# umotion_2_v1_2_pcb_1.net
KiCad netlist of a schematic drawn in EAGLE
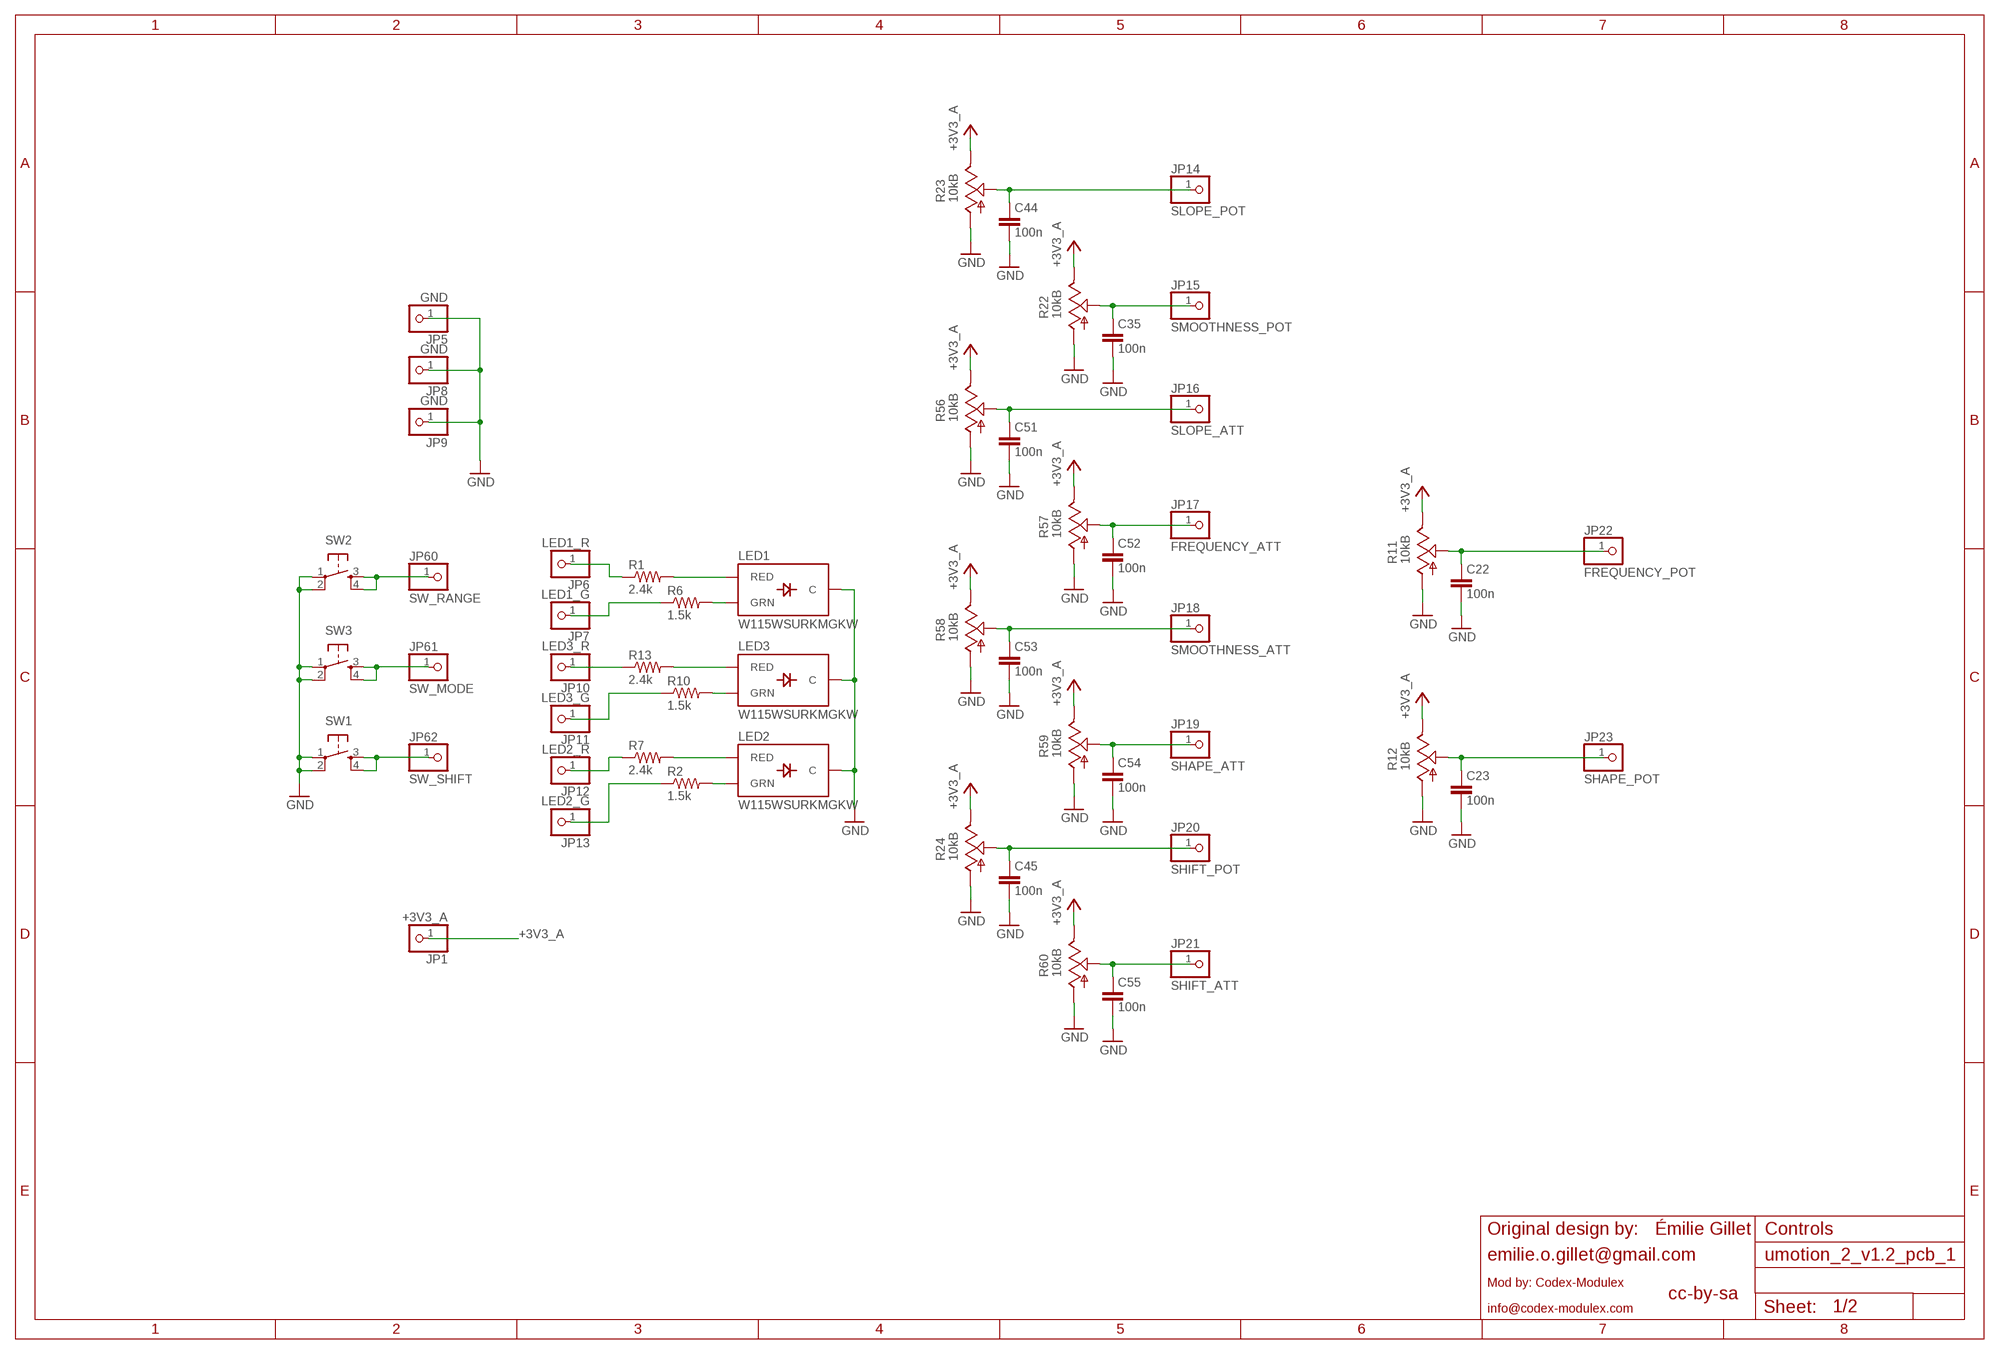
[diagram p0: schematic, sheet 1]
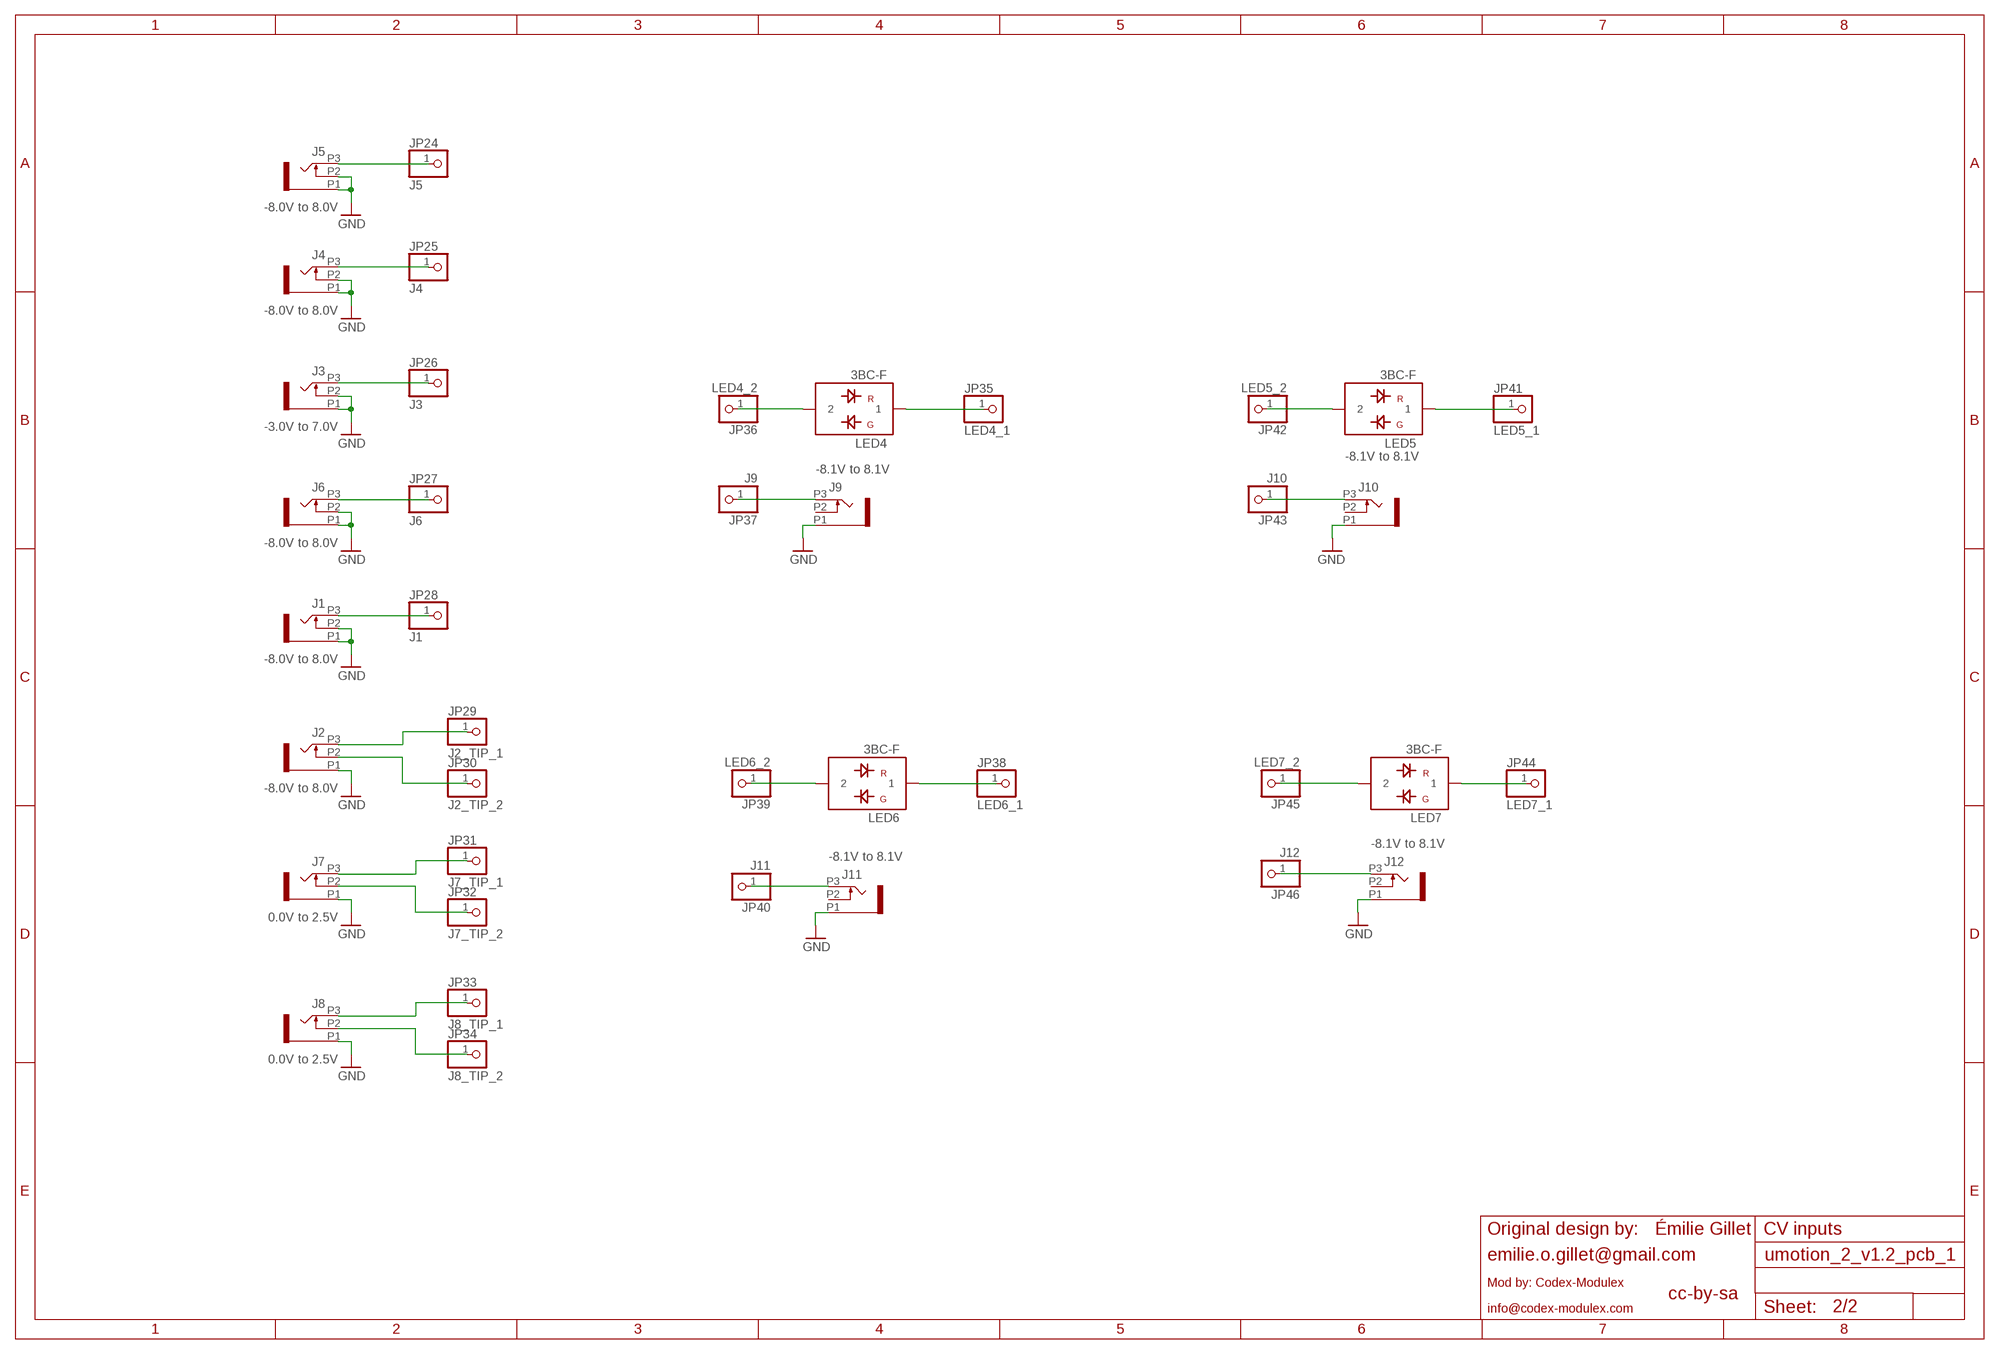
[diagram p1: schematic, sheet 2]

(export (version "E")
  (design (tool "Eeschema 10.0.6"))
  (components
    (comp (ref "J1")
      (value "PJ301_THONKICONN6")
      (footprint "eagle-import:WQP_PJ_301M6")
      (libsource (lib "eagle-import") (part "og-pj301_variations_PJ301_THONKICONN6"))
    )
    (comp (ref "J2")
      (value "PJ301_THONKICONN6")
      (footprint "eagle-import:WQP_PJ_301M6")
      (libsource (lib "eagle-import") (part "og-pj301_variations_PJ301_THONKICONN6"))
    )
    (comp (ref "J3")
      (value "PJ301_THONKICONN6")
      (footprint "eagle-import:WQP_PJ_301M6")
      (libsource (lib "eagle-import") (part "og-pj301_variations_PJ301_THONKICONN6"))
    )
    (comp (ref "J4")
      (value "PJ301_THONKICONN6")
      (footprint "eagle-import:WQP_PJ_301M6")
      (libsource (lib "eagle-import") (part "og-pj301_variations_PJ301_THONKICONN6"))
    )
    (comp (ref "J5")
      (value "PJ301_THONKICONN6")
      (footprint "eagle-import:WQP_PJ_301M6")
      (libsource (lib "eagle-import") (part "og-pj301_variations_PJ301_THONKICONN6"))
    )
    (comp (ref "J6")
      (value "PJ301_THONKICONN6")
      (footprint "eagle-import:WQP_PJ_301M6")
      (libsource (lib "eagle-import") (part "og-pj301_variations_PJ301_THONKICONN6"))
    )
    (comp (ref "J7")
      (value "PJ301_THONKICONN6")
      (footprint "eagle-import:WQP_PJ_301M6")
      (libsource (lib "eagle-import") (part "og-pj301_variations_PJ301_THONKICONN6"))
    )
    (comp (ref "J8")
      (value "PJ301_THONKICONN6")
      (footprint "eagle-import:WQP_PJ_301M6")
      (libsource (lib "eagle-import") (part "og-pj301_variations_PJ301_THONKICONN6"))
    )
    (comp (ref "J9")
      (value "PJ301_THONKICONN6")
      (footprint "eagle-import:WQP_PJ_301M6")
      (libsource (lib "eagle-import") (part "PJ301_THONKICONN6"))
    )
    (comp (ref "J10")
      (value "PJ301_THONKICONN6")
      (footprint "eagle-import:WQP_PJ_301M6")
      (libsource (lib "eagle-import") (part "PJ301_THONKICONN6"))
    )
    (comp (ref "J11")
      (value "PJ301_THONKICONN6")
      (footprint "eagle-import:WQP_PJ_301M6")
      (libsource (lib "eagle-import") (part "PJ301_THONKICONN6"))
    )
    (comp (ref "J12")
      (value "PJ301_THONKICONN6")
      (footprint "eagle-import:WQP_PJ_301M6")
      (libsource (lib "eagle-import") (part "PJ301_THONKICONN6"))
    )
    (comp (ref "JP24")
      (value "J5")
      (footprint "eagle-import:PARTS_AMAN_1X01")
      (libsource (lib "eagle-import") (part "PARTS_AMAN_PINHD-1X1"))
    )
    (comp (ref "JP25")
      (value "J4")
      (footprint "eagle-import:PARTS_AMAN_1X01")
      (libsource (lib "eagle-import") (part "PARTS_AMAN_PINHD-1X1"))
    )
    (comp (ref "JP26")
      (value "J3")
      (footprint "eagle-import:PARTS_AMAN_1X01")
      (libsource (lib "eagle-import") (part "PARTS_AMAN_PINHD-1X1"))
    )
    (comp (ref "JP27")
      (value "J6")
      (footprint "eagle-import:PARTS_AMAN_1X01")
      (libsource (lib "eagle-import") (part "PARTS_AMAN_PINHD-1X1"))
    )
    (comp (ref "JP28")
      (value "J1")
      (footprint "eagle-import:PARTS_AMAN_1X01")
      (libsource (lib "eagle-import") (part "PARTS_AMAN_PINHD-1X1"))
    )
    (comp (ref "JP29")
      (value "J2_TIP_1")
      (footprint "eagle-import:PARTS_AMAN_1X01")
      (libsource (lib "eagle-import") (part "PARTS_AMAN_PINHD-1X1"))
    )
    (comp (ref "JP30")
      (value "J2_TIP_2")
      (footprint "eagle-import:PARTS_AMAN_1X01")
      (libsource (lib "eagle-import") (part "PARTS_AMAN_PINHD-1X1"))
    )
    (comp (ref "JP31")
      (value "J7_TIP_1")
      (footprint "eagle-import:PARTS_AMAN_1X01")
      (libsource (lib "eagle-import") (part "PARTS_AMAN_PINHD-1X1"))
    )
    (comp (ref "JP32")
      (value "J7_TIP_2")
      (footprint "eagle-import:PARTS_AMAN_1X01")
      (libsource (lib "eagle-import") (part "PARTS_AMAN_PINHD-1X1"))
    )
    (comp (ref "JP33")
      (value "J8_TIP_1")
      (footprint "eagle-import:PARTS_AMAN_1X01")
      (libsource (lib "eagle-import") (part "PARTS_AMAN_PINHD-1X1"))
    )
    (comp (ref "JP34")
      (value "J8_TIP_2")
      (footprint "eagle-import:PARTS_AMAN_1X01")
      (libsource (lib "eagle-import") (part "PARTS_AMAN_PINHD-1X1"))
    )
    (comp (ref "JP35")
      (value "LED4_1")
      (footprint "eagle-import:PARTS_AMAN_1X01")
      (libsource (lib "eagle-import") (part "PARTS_AMAN_PINHD-1X1"))
    )
    (comp (ref "JP36")
      (value "LED4_2")
      (footprint "eagle-import:PARTS_AMAN_1X01")
      (libsource (lib "eagle-import") (part "PARTS_AMAN_PINHD-1X1"))
    )
    (comp (ref "JP37")
      (value "J9")
      (footprint "eagle-import:PARTS_AMAN_1X01")
      (libsource (lib "eagle-import") (part "PARTS_AMAN_PINHD-1X1"))
    )
    (comp (ref "JP38")
      (value "LED6_1")
      (footprint "eagle-import:PARTS_AMAN_1X01")
      (libsource (lib "eagle-import") (part "PARTS_AMAN_PINHD-1X1"))
    )
    (comp (ref "JP39")
      (value "LED6_2")
      (footprint "eagle-import:PARTS_AMAN_1X01")
      (libsource (lib "eagle-import") (part "PARTS_AMAN_PINHD-1X1"))
    )
    (comp (ref "JP40")
      (value "J11")
      (footprint "eagle-import:PARTS_AMAN_1X01")
      (libsource (lib "eagle-import") (part "PARTS_AMAN_PINHD-1X1"))
    )
    (comp (ref "JP41")
      (value "LED5_1")
      (footprint "eagle-import:PARTS_AMAN_1X01")
      (libsource (lib "eagle-import") (part "PARTS_AMAN_PINHD-1X1"))
    )
    (comp (ref "JP42")
      (value "LED5_2")
      (footprint "eagle-import:PARTS_AMAN_1X01")
      (libsource (lib "eagle-import") (part "PARTS_AMAN_PINHD-1X1"))
    )
    (comp (ref "JP43")
      (value "J10")
      (footprint "eagle-import:PARTS_AMAN_1X01")
      (libsource (lib "eagle-import") (part "PARTS_AMAN_PINHD-1X1"))
    )
    (comp (ref "JP44")
      (value "LED7_1")
      (footprint "eagle-import:PARTS_AMAN_1X01")
      (libsource (lib "eagle-import") (part "PARTS_AMAN_PINHD-1X1"))
    )
    (comp (ref "JP45")
      (value "LED7_2")
      (footprint "eagle-import:PARTS_AMAN_1X01")
      (libsource (lib "eagle-import") (part "PARTS_AMAN_PINHD-1X1"))
    )
    (comp (ref "JP46")
      (value "J12")
      (footprint "eagle-import:PARTS_AMAN_1X01")
      (libsource (lib "eagle-import") (part "PARTS_AMAN_PINHD-1X1"))
    )
    (comp (ref "LED4")
      (value "3BC-F")
      (footprint "eagle-import:LED3MM")
      (libsource (lib "eagle-import") (part "LED-BICOLOR-SHARED-THROUGHHOLE"))
    )
    (comp (ref "LED5")
      (value "3BC-F")
      (footprint "eagle-import:LED3MM")
      (libsource (lib "eagle-import") (part "LED-BICOLOR-SHARED-THROUGHHOLE"))
    )
    (comp (ref "LED6")
      (value "3BC-F")
      (footprint "eagle-import:LED3MM")
      (libsource (lib "eagle-import") (part "LED-BICOLOR-SHARED-THROUGHHOLE"))
    )
    (comp (ref "LED7")
      (value "3BC-F")
      (footprint "eagle-import:LED3MM")
      (libsource (lib "eagle-import") (part "LED-BICOLOR-SHARED-THROUGHHOLE"))
    )
    (comp (ref "C22")
      (value "100n")
      (footprint "eagle-import:PARTS_AMAN_RESISTOR_0603")
      (libsource (lib "eagle-import") (part "PARTS_AMAN_CAPACITOR"))
    )
    (comp (ref "C23")
      (value "100n")
      (footprint "eagle-import:PARTS_AMAN_RESISTOR_0603")
      (libsource (lib "eagle-import") (part "PARTS_AMAN_CAPACITOR"))
    )
    (comp (ref "C35")
      (value "100n")
      (footprint "eagle-import:PARTS_AMAN_RESISTOR_0603")
      (libsource (lib "eagle-import") (part "PARTS_AMAN_CAPACITOR"))
    )
    (comp (ref "C44")
      (value "100n")
      (footprint "eagle-import:PARTS_AMAN_RESISTOR_0603")
      (libsource (lib "eagle-import") (part "PARTS_AMAN_CAPACITOR"))
    )
    (comp (ref "C45")
      (value "100n")
      (footprint "eagle-import:PARTS_AMAN_RESISTOR_0603")
      (libsource (lib "eagle-import") (part "PARTS_AMAN_CAPACITOR"))
    )
    (comp (ref "C51")
      (value "100n")
      (footprint "eagle-import:PARTS_AMAN_RESISTOR_0603")
      (libsource (lib "eagle-import") (part "PARTS_AMAN_CAPACITOR"))
    )
    (comp (ref "C52")
      (value "100n")
      (footprint "eagle-import:PARTS_AMAN_RESISTOR_0603")
      (libsource (lib "eagle-import") (part "PARTS_AMAN_CAPACITOR"))
    )
    (comp (ref "C53")
      (value "100n")
      (footprint "eagle-import:PARTS_AMAN_RESISTOR_0603")
      (libsource (lib "eagle-import") (part "PARTS_AMAN_CAPACITOR"))
    )
    (comp (ref "C54")
      (value "100n")
      (footprint "eagle-import:PARTS_AMAN_RESISTOR_0603")
      (libsource (lib "eagle-import") (part "PARTS_AMAN_CAPACITOR"))
    )
    (comp (ref "C55")
      (value "100n")
      (footprint "eagle-import:PARTS_AMAN_RESISTOR_0603")
      (libsource (lib "eagle-import") (part "PARTS_AMAN_CAPACITOR"))
    )
    (comp (ref "JP1")
      (value "+3V3_A")
      (footprint "eagle-import:PARTS_AMAN_1X01")
      (libsource (lib "eagle-import") (part "PARTS_AMAN_PINHD-1X1"))
    )
    (comp (ref "JP5")
      (value "GND")
      (footprint "eagle-import:PARTS_AMAN_1X01")
      (libsource (lib "eagle-import") (part "PARTS_AMAN_PINHD-1X1"))
    )
    (comp (ref "JP6")
      (value "LED1_R")
      (footprint "eagle-import:PARTS_AMAN_1X01")
      (libsource (lib "eagle-import") (part "PARTS_AMAN_PINHD-1X1"))
    )
    (comp (ref "JP7")
      (value "LED1_G")
      (footprint "eagle-import:PARTS_AMAN_1X01")
      (libsource (lib "eagle-import") (part "PARTS_AMAN_PINHD-1X1"))
    )
    (comp (ref "JP8")
      (value "GND")
      (footprint "eagle-import:PARTS_AMAN_1X01")
      (libsource (lib "eagle-import") (part "PARTS_AMAN_PINHD-1X1"))
    )
    (comp (ref "JP9")
      (value "GND")
      (footprint "eagle-import:PARTS_AMAN_1X01")
      (libsource (lib "eagle-import") (part "PARTS_AMAN_PINHD-1X1"))
    )
    (comp (ref "JP10")
      (value "LED3_R")
      (footprint "eagle-import:PARTS_AMAN_1X01")
      (libsource (lib "eagle-import") (part "PARTS_AMAN_PINHD-1X1"))
    )
    (comp (ref "JP11")
      (value "LED3_G")
      (footprint "eagle-import:PARTS_AMAN_1X01")
      (libsource (lib "eagle-import") (part "PARTS_AMAN_PINHD-1X1"))
    )
    (comp (ref "JP12")
      (value "LED2_R")
      (footprint "eagle-import:PARTS_AMAN_1X01")
      (libsource (lib "eagle-import") (part "PARTS_AMAN_PINHD-1X1"))
    )
    (comp (ref "JP13")
      (value "LED2_G")
      (footprint "eagle-import:PARTS_AMAN_1X01")
      (libsource (lib "eagle-import") (part "PARTS_AMAN_PINHD-1X1"))
    )
    (comp (ref "JP14")
      (value "SLOPE_POT")
      (footprint "eagle-import:PARTS_AMAN_1X01")
      (libsource (lib "eagle-import") (part "PARTS_AMAN_PINHD-1X1"))
    )
    (comp (ref "JP15")
      (value "SMOOTHNESS_POT")
      (footprint "eagle-import:PARTS_AMAN_1X01")
      (libsource (lib "eagle-import") (part "PARTS_AMAN_PINHD-1X1"))
    )
    (comp (ref "JP16")
      (value "SLOPE_ATT")
      (footprint "eagle-import:PARTS_AMAN_1X01")
      (libsource (lib "eagle-import") (part "PARTS_AMAN_PINHD-1X1"))
    )
    (comp (ref "JP17")
      (value "FREQUENCY_ATT")
      (footprint "eagle-import:PARTS_AMAN_1X01")
      (libsource (lib "eagle-import") (part "PARTS_AMAN_PINHD-1X1"))
    )
    (comp (ref "JP18")
      (value "SMOOTHNESS_ATT")
      (footprint "eagle-import:PARTS_AMAN_1X01")
      (libsource (lib "eagle-import") (part "PARTS_AMAN_PINHD-1X1"))
    )
    (comp (ref "JP19")
      (value "SHAPE_ATT")
      (footprint "eagle-import:PARTS_AMAN_1X01")
      (libsource (lib "eagle-import") (part "PARTS_AMAN_PINHD-1X1"))
    )
    (comp (ref "JP20")
      (value "SHIFT_POT")
      (footprint "eagle-import:PARTS_AMAN_1X01")
      (libsource (lib "eagle-import") (part "PARTS_AMAN_PINHD-1X1"))
    )
    (comp (ref "JP21")
      (value "SHIFT_ATT")
      (footprint "eagle-import:PARTS_AMAN_1X01")
      (libsource (lib "eagle-import") (part "PARTS_AMAN_PINHD-1X1"))
    )
    (comp (ref "JP22")
      (value "FREQUENCY_POT")
      (footprint "eagle-import:PARTS_AMAN_1X01")
      (libsource (lib "eagle-import") (part "PARTS_AMAN_PINHD-1X1"))
    )
    (comp (ref "JP23")
      (value "SHAPE_POT")
      (footprint "eagle-import:PARTS_AMAN_1X01")
      (libsource (lib "eagle-import") (part "PARTS_AMAN_PINHD-1X1"))
    )
    (comp (ref "JP60")
      (value "SW_RANGE")
      (footprint "eagle-import:PARTS_AMAN_1X01")
      (libsource (lib "eagle-import") (part "PARTS_AMAN_PINHD-1X1"))
    )
    (comp (ref "JP61")
      (value "SW_MODE")
      (footprint "eagle-import:PARTS_AMAN_1X01")
      (libsource (lib "eagle-import") (part "PARTS_AMAN_PINHD-1X1"))
    )
    (comp (ref "JP62")
      (value "SW_SHIFT")
      (footprint "eagle-import:PARTS_AMAN_1X01")
      (libsource (lib "eagle-import") (part "PARTS_AMAN_PINHD-1X1"))
    )
    (comp (ref "LED1")
      (value "W115WSURKMGKW")
      (footprint "eagle-import:LED-BICOLOR-THROUGHHOLE-2.54")
      (libsource (lib "eagle-import") (part "LED-BICOLOR-THROUGHHOLE2.54"))
    )
    (comp (ref "LED2")
      (value "W115WSURKMGKW")
      (footprint "eagle-import:LED-BICOLOR-THROUGHHOLE-2.54")
      (libsource (lib "eagle-import") (part "LED-BICOLOR-THROUGHHOLE2.54"))
    )
    (comp (ref "LED3")
      (value "W115WSURKMGKW")
      (footprint "eagle-import:LED-BICOLOR-THROUGHHOLE-2.54")
      (libsource (lib "eagle-import") (part "LED-BICOLOR-THROUGHHOLE2.54"))
    )
    (comp (ref "R1")
      (value "2.4k")
      (footprint "eagle-import:PARTS_AMAN_RESISTOR_0603")
      (libsource (lib "eagle-import") (part "PARTS_AMAN_RESISTOR"))
    )
    (comp (ref "R2")
      (value "1.5k")
      (footprint "eagle-import:PARTS_AMAN_RESISTOR_0603")
      (libsource (lib "eagle-import") (part "PARTS_AMAN_RESISTOR"))
    )
    (comp (ref "R6")
      (value "1.5k")
      (footprint "eagle-import:PARTS_AMAN_RESISTOR_0603")
      (libsource (lib "eagle-import") (part "PARTS_AMAN_RESISTOR"))
    )
    (comp (ref "R7")
      (value "2.4k")
      (footprint "eagle-import:PARTS_AMAN_RESISTOR_0603")
      (libsource (lib "eagle-import") (part "PARTS_AMAN_RESISTOR"))
    )
    (comp (ref "R10")
      (value "1.5k")
      (footprint "eagle-import:PARTS_AMAN_RESISTOR_0603")
      (libsource (lib "eagle-import") (part "PARTS_AMAN_RESISTOR"))
    )
    (comp (ref "R11")
      (value "10kB")
      (footprint "eagle-import:ALPS_POT_VERTICAL")
      (libsource (lib "eagle-import") (part "POT_USVERTICAL"))
    )
    (comp (ref "R12")
      (value "10kB")
      (footprint "eagle-import:ALPS_POT_VERTICAL")
      (libsource (lib "eagle-import") (part "POT_USVERTICAL"))
    )
    (comp (ref "R13")
      (value "2.4k")
      (footprint "eagle-import:PARTS_AMAN_RESISTOR_0603")
      (libsource (lib "eagle-import") (part "PARTS_AMAN_RESISTOR"))
    )
    (comp (ref "R22")
      (value "10kB")
      (footprint "eagle-import:ALPS_POT_VERTICAL")
      (libsource (lib "eagle-import") (part "POT_USVERTICAL"))
    )
    (comp (ref "R23")
      (value "10kB")
      (footprint "eagle-import:ALPS_POT_VERTICAL")
      (libsource (lib "eagle-import") (part "POT_USVERTICAL"))
    )
    (comp (ref "R24")
      (value "10kB")
      (footprint "eagle-import:ALPS_POT_VERTICAL")
      (libsource (lib "eagle-import") (part "POT_USVERTICAL"))
    )
    (comp (ref "R56")
      (value "10kB")
      (footprint "eagle-import:ALPS_POT_VERTICAL")
      (libsource (lib "eagle-import") (part "POT_USVERTICAL"))
    )
    (comp (ref "R57")
      (value "10kB")
      (footprint "eagle-import:ALPS_POT_VERTICAL")
      (libsource (lib "eagle-import") (part "POT_USVERTICAL"))
    )
    (comp (ref "R58")
      (value "10kB")
      (footprint "eagle-import:ALPS_POT_VERTICAL")
      (libsource (lib "eagle-import") (part "POT_USVERTICAL"))
    )
    (comp (ref "R59")
      (value "10kB")
      (footprint "eagle-import:ALPS_POT_VERTICAL")
      (libsource (lib "eagle-import") (part "POT_USVERTICAL"))
    )
    (comp (ref "R60")
      (value "10kB")
      (footprint "eagle-import:ALPS_POT_VERTICAL")
      (libsource (lib "eagle-import") (part "POT_USVERTICAL"))
    )
    (comp (ref "SW1")
      (value "TAC_SWITCHPTH")
      (footprint "eagle-import:TACTILE-PTH")
      (libsource (lib "eagle-import") (part "TAC_SWITCHPTH"))
    )
    (comp (ref "SW2")
      (value "TAC_SWITCHPTH")
      (footprint "eagle-import:TACTILE-PTH")
      (libsource (lib "eagle-import") (part "TAC_SWITCHPTH"))
    )
    (comp (ref "SW3")
      (value "TAC_SWITCHPTH")
      (footprint "eagle-import:TACTILE-PTH")
      (libsource (lib "eagle-import") (part "TAC_SWITCHPTH"))
    )
  )
  (nets
    (net (code "1") (name "+3V3_A") (class "Default")
      (node (ref "JP1") (pin "1") (pinfunction "1_1") (pintype "passive"))
      (node (ref "R11") (pin "P$1") (pinfunction "E_P$1") (pintype "passive"))
      (node (ref "R12") (pin "P$1") (pinfunction "E_P$1") (pintype "passive"))
      (node (ref "R22") (pin "P$1") (pinfunction "E_P$1") (pintype "passive"))
      (node (ref "R23") (pin "P$1") (pinfunction "E_P$1") (pintype "passive"))
      (node (ref "R24") (pin "P$1") (pinfunction "E_P$1") (pintype "passive"))
      (node (ref "R56") (pin "P$1") (pinfunction "E_P$1") (pintype "passive"))
      (node (ref "R57") (pin "P$1") (pinfunction "E_P$1") (pintype "passive"))
      (node (ref "R58") (pin "P$1") (pinfunction "E_P$1") (pintype "passive"))
      (node (ref "R59") (pin "P$1") (pinfunction "E_P$1") (pintype "passive"))
      (node (ref "R60") (pin "P$1") (pinfunction "E_P$1") (pintype "passive"))
    )
    (net (code "2") (name "GND") (class "Default")
      (node (ref "C22") (pin "2") (pinfunction "2_2") (pintype "passive"))
      (node (ref "C23") (pin "2") (pinfunction "2_2") (pintype "passive"))
      (node (ref "C35") (pin "2") (pinfunction "2_2") (pintype "passive"))
      (node (ref "C44") (pin "2") (pinfunction "2_2") (pintype "passive"))
      (node (ref "C45") (pin "2") (pinfunction "2_2") (pintype "passive"))
      (node (ref "C51") (pin "2") (pinfunction "2_2") (pintype "passive"))
      (node (ref "C52") (pin "2") (pinfunction "2_2") (pintype "passive"))
      (node (ref "C53") (pin "2") (pinfunction "2_2") (pintype "passive"))
      (node (ref "C54") (pin "2") (pinfunction "2_2") (pintype "passive"))
      (node (ref "C55") (pin "2") (pinfunction "2_2") (pintype "passive"))
      (node (ref "J1") (pin "P1") (pinfunction "1_P1") (pintype "passive"))
      (node (ref "J1") (pin "P2") (pinfunction "2_P2") (pintype "passive"))
      (node (ref "J10") (pin "P1") (pinfunction "1_P1") (pintype "passive"))
      (node (ref "J11") (pin "P1") (pinfunction "1_P1") (pintype "passive"))
      (node (ref "J12") (pin "P1") (pinfunction "1_P1") (pintype "passive"))
      (node (ref "J2") (pin "P1") (pinfunction "1_P1") (pintype "passive"))
      (node (ref "J3") (pin "P1") (pinfunction "1_P1") (pintype "passive"))
      (node (ref "J3") (pin "P2") (pinfunction "2_P2") (pintype "passive"))
      (node (ref "J4") (pin "P1") (pinfunction "1_P1") (pintype "passive"))
      (node (ref "J4") (pin "P2") (pinfunction "2_P2") (pintype "passive"))
      (node (ref "J5") (pin "P1") (pinfunction "1_P1") (pintype "passive"))
      (node (ref "J5") (pin "P2") (pinfunction "2_P2") (pintype "passive"))
      (node (ref "J6") (pin "P1") (pinfunction "1_P1") (pintype "passive"))
      (node (ref "J6") (pin "P2") (pinfunction "2_P2") (pintype "passive"))
      (node (ref "J7") (pin "P1") (pinfunction "1_P1") (pintype "passive"))
      (node (ref "J8") (pin "P1") (pinfunction "1_P1") (pintype "passive"))
      (node (ref "J9") (pin "P1") (pinfunction "1_P1") (pintype "passive"))
      (node (ref "JP5") (pin "1") (pinfunction "1_1") (pintype "passive"))
      (node (ref "JP8") (pin "1") (pinfunction "1_1") (pintype "passive"))
      (node (ref "JP9") (pin "1") (pinfunction "1_1") (pintype "passive"))
      (node (ref "LED1") (pin "2") (pinfunction "C_2") (pintype "bidirectional"))
      (node (ref "LED2") (pin "2") (pinfunction "C_2") (pintype "bidirectional"))
      (node (ref "LED3") (pin "2") (pinfunction "C_2") (pintype "bidirectional"))
      (node (ref "R11") (pin "P$3") (pinfunction "A_P$3") (pintype "passive"))
      (node (ref "R12") (pin "P$3") (pinfunction "A_P$3") (pintype "passive"))
      (node (ref "R22") (pin "P$3") (pinfunction "A_P$3") (pintype "passive"))
      (node (ref "R23") (pin "P$3") (pinfunction "A_P$3") (pintype "passive"))
      (node (ref "R24") (pin "P$3") (pinfunction "A_P$3") (pintype "passive"))
      (node (ref "R56") (pin "P$3") (pinfunction "A_P$3") (pintype "passive"))
      (node (ref "R57") (pin "P$3") (pinfunction "A_P$3") (pintype "passive"))
      (node (ref "R58") (pin "P$3") (pinfunction "A_P$3") (pintype "passive"))
      (node (ref "R59") (pin "P$3") (pinfunction "A_P$3") (pintype "passive"))
      (node (ref "R60") (pin "P$3") (pinfunction "A_P$3") (pintype "passive"))
      (node (ref "SW1") (pin "1") (pinfunction "1_1") (pintype "passive"))
      (node (ref "SW1") (pin "2") (pinfunction "2_2") (pintype "passive"))
      (node (ref "SW2") (pin "1") (pinfunction "1_1") (pintype "passive"))
      (node (ref "SW2") (pin "2") (pinfunction "2_2") (pintype "passive"))
      (node (ref "SW3") (pin "1") (pinfunction "1_1") (pintype "passive"))
      (node (ref "SW3") (pin "2") (pinfunction "2_2") (pintype "passive"))
    )
    (net (code "3") (name "Net-(J1-3)") (class "Default")
      (node (ref "J1") (pin "P3") (pinfunction "3_P3") (pintype "passive"))
      (node (ref "JP28") (pin "1") (pinfunction "1_1") (pintype "passive"))
    )
    (net (code "4") (name "Net-(J2-2)") (class "Default")
      (node (ref "J2") (pin "P2") (pinfunction "2_P2") (pintype "passive"))
      (node (ref "JP30") (pin "1") (pinfunction "1_1") (pintype "passive"))
    )
    (net (code "5") (name "Net-(J2-3)") (class "Default")
      (node (ref "J2") (pin "P3") (pinfunction "3_P3") (pintype "passive"))
      (node (ref "JP29") (pin "1") (pinfunction "1_1") (pintype "passive"))
    )
    (net (code "6") (name "Net-(J3-3)") (class "Default")
      (node (ref "J3") (pin "P3") (pinfunction "3_P3") (pintype "passive"))
      (node (ref "JP26") (pin "1") (pinfunction "1_1") (pintype "passive"))
    )
    (net (code "7") (name "Net-(J4-3)") (class "Default")
      (node (ref "J4") (pin "P3") (pinfunction "3_P3") (pintype "passive"))
      (node (ref "JP25") (pin "1") (pinfunction "1_1") (pintype "passive"))
    )
    (net (code "8") (name "Net-(J5-3)") (class "Default")
      (node (ref "J5") (pin "P3") (pinfunction "3_P3") (pintype "passive"))
      (node (ref "JP24") (pin "1") (pinfunction "1_1") (pintype "passive"))
    )
    (net (code "9") (name "Net-(J6-3)") (class "Default")
      (node (ref "J6") (pin "P3") (pinfunction "3_P3") (pintype "passive"))
      (node (ref "JP27") (pin "1") (pinfunction "1_1") (pintype "passive"))
    )
    (net (code "10") (name "Net-(J7-2)") (class "Default")
      (node (ref "J7") (pin "P2") (pinfunction "2_P2") (pintype "passive"))
      (node (ref "JP32") (pin "1") (pinfunction "1_1") (pintype "passive"))
    )
    (net (code "11") (name "Net-(J7-3)") (class "Default")
      (node (ref "J7") (pin "P3") (pinfunction "3_P3") (pintype "passive"))
      (node (ref "JP31") (pin "1") (pinfunction "1_1") (pintype "passive"))
    )
    (net (code "12") (name "Net-(J8-2)") (class "Default")
      (node (ref "J8") (pin "P2") (pinfunction "2_P2") (pintype "passive"))
      (node (ref "JP34") (pin "1") (pinfunction "1_1") (pintype "passive"))
    )
    (net (code "13") (name "Net-(J8-3)") (class "Default")
      (node (ref "J8") (pin "P3") (pinfunction "3_P3") (pintype "passive"))
      (node (ref "JP33") (pin "1") (pinfunction "1_1") (pintype "passive"))
    )
    (net (code "14") (name "Net-(J9-3)") (class "Default")
      (node (ref "J9") (pin "P3") (pinfunction "3_P3") (pintype "passive"))
      (node (ref "JP37") (pin "1") (pinfunction "1_1") (pintype "passive"))
    )
    (net (code "15") (name "Net-(J10-3)") (class "Default")
      (node (ref "J10") (pin "P3") (pinfunction "3_P3") (pintype "passive"))
      (node (ref "JP43") (pin "1") (pinfunction "1_1") (pintype "passive"))
    )
    (net (code "16") (name "Net-(J11-3)") (class "Default")
      (node (ref "J11") (pin "P3") (pinfunction "3_P3") (pintype "passive"))
      (node (ref "JP40") (pin "1") (pinfunction "1_1") (pintype "passive"))
    )
    (net (code "17") (name "Net-(J12-3)") (class "Default")
      (node (ref "J12") (pin "P3") (pinfunction "3_P3") (pintype "passive"))
      (node (ref "JP46") (pin "1") (pinfunction "1_1") (pintype "passive"))
    )
    (net (code "18") (name "Net-(JP6-Pad1)") (class "Default")
      (node (ref "JP6") (pin "1") (pinfunction "1_1") (pintype "passive"))
      (node (ref "R1") (pin "1") (pinfunction "1_1") (pintype "passive"))
    )
    (net (code "19") (name "Net-(JP7-Pad1)") (class "Default")
      (node (ref "JP7") (pin "1") (pinfunction "1_1") (pintype "passive"))
      (node (ref "R6") (pin "1") (pinfunction "1_1") (pintype "passive"))
    )
    (net (code "20") (name "Net-(JP10-Pad1)") (class "Default")
      (node (ref "JP10") (pin "1") (pinfunction "1_1") (pintype "passive"))
      (node (ref "R13") (pin "1") (pinfunction "1_1") (pintype "passive"))
    )
    (net (code "21") (name "Net-(JP11-Pad1)") (class "Default")
      (node (ref "JP11") (pin "1") (pinfunction "1_1") (pintype "passive"))
      (node (ref "R10") (pin "1") (pinfunction "1_1") (pintype "passive"))
    )
    (net (code "22") (name "Net-(JP12-Pad1)") (class "Default")
      (node (ref "JP12") (pin "1") (pinfunction "1_1") (pintype "passive"))
      (node (ref "R7") (pin "1") (pinfunction "1_1") (pintype "passive"))
    )
    (net (code "23") (name "Net-(JP13-Pad1)") (class "Default")
      (node (ref "JP13") (pin "1") (pinfunction "1_1") (pintype "passive"))
      (node (ref "R2") (pin "1") (pinfunction "1_1") (pintype "passive"))
    )
    (net (code "24") (name "Net-(JP35-Pad1)") (class "Default")
      (node (ref "JP35") (pin "1") (pinfunction "1_1") (pintype "passive"))
      (node (ref "LED4") (pin "1") (pinfunction "1_1") (pintype "bidirectional"))
    )
    (net (code "25") (name "Net-(JP36-Pad1)") (class "Default")
      (node (ref "JP36") (pin "1") (pinfunction "1_1") (pintype "passive"))
      (node (ref "LED4") (pin "2") (pinfunction "2_2") (pintype "bidirectional"))
    )
    (net (code "26") (name "Net-(JP38-Pad1)") (class "Default")
      (node (ref "JP38") (pin "1") (pinfunction "1_1") (pintype "passive"))
      (node (ref "LED6") (pin "1") (pinfunction "1_1") (pintype "bidirectional"))
    )
    (net (code "27") (name "Net-(JP39-Pad1)") (class "Default")
      (node (ref "JP39") (pin "1") (pinfunction "1_1") (pintype "passive"))
      (node (ref "LED6") (pin "2") (pinfunction "2_2") (pintype "bidirectional"))
    )
    (net (code "28") (name "Net-(JP41-Pad1)") (class "Default")
      (node (ref "JP41") (pin "1") (pinfunction "1_1") (pintype "passive"))
      (node (ref "LED5") (pin "1") (pinfunction "1_1") (pintype "bidirectional"))
    )
    (net (code "29") (name "Net-(JP42-Pad1)") (class "Default")
      (node (ref "JP42") (pin "1") (pinfunction "1_1") (pintype "passive"))
      (node (ref "LED5") (pin "2") (pinfunction "2_2") (pintype "bidirectional"))
    )
    (net (code "30") (name "Net-(JP44-Pad1)") (class "Default")
      (node (ref "JP44") (pin "1") (pinfunction "1_1") (pintype "passive"))
      (node (ref "LED7") (pin "1") (pinfunction "1_1") (pintype "bidirectional"))
    )
    (net (code "31") (name "Net-(JP45-Pad1)") (class "Default")
      (node (ref "JP45") (pin "1") (pinfunction "1_1") (pintype "passive"))
      (node (ref "LED7") (pin "2") (pinfunction "2_2") (pintype "bidirectional"))
    )
    (net (code "32") (name "Net-(JP60-Pad1)") (class "Default")
      (node (ref "JP60") (pin "1") (pinfunction "1_1") (pintype "passive"))
      (node (ref "SW2") (pin "3") (pinfunction "3_3") (pintype "passive"))
      (node (ref "SW2") (pin "4") (pinfunction "4_4") (pintype "passive"))
    )
    (net (code "33") (name "Net-(JP61-Pad1)") (class "Default")
      (node (ref "JP61") (pin "1") (pinfunction "1_1") (pintype "passive"))
      (node (ref "SW3") (pin "3") (pinfunction "3_3") (pintype "passive"))
      (node (ref "SW3") (pin "4") (pinfunction "4_4") (pintype "passive"))
    )
    (net (code "34") (name "Net-(JP62-Pad1)") (class "Default")
      (node (ref "JP62") (pin "1") (pinfunction "1_1") (pintype "passive"))
      (node (ref "SW1") (pin "3") (pinfunction "3_3") (pintype "passive"))
      (node (ref "SW1") (pin "4") (pinfunction "4_4") (pintype "passive"))
    )
    (net (code "35") (name "Net-(LED1-GRN)") (class "Default")
      (node (ref "LED1") (pin "1") (pinfunction "GRN_1") (pintype "bidirectional"))
      (node (ref "R6") (pin "2") (pinfunction "2_2") (pintype "passive"))
    )
    (net (code "36") (name "Net-(LED1-RED)") (class "Default")
      (node (ref "LED1") (pin "3") (pinfunction "RED_3") (pintype "bidirectional"))
      (node (ref "R1") (pin "2") (pinfunction "2_2") (pintype "passive"))
    )
    (net (code "37") (name "Net-(LED2-GRN)") (class "Default")
      (node (ref "LED2") (pin "1") (pinfunction "GRN_1") (pintype "bidirectional"))
      (node (ref "R2") (pin "2") (pinfunction "2_2") (pintype "passive"))
    )
    (net (code "38") (name "Net-(LED2-RED)") (class "Default")
      (node (ref "LED2") (pin "3") (pinfunction "RED_3") (pintype "bidirectional"))
      (node (ref "R7") (pin "2") (pinfunction "2_2") (pintype "passive"))
    )
    (net (code "39") (name "Net-(LED3-GRN)") (class "Default")
      (node (ref "LED3") (pin "1") (pinfunction "GRN_1") (pintype "bidirectional"))
      (node (ref "R10") (pin "2") (pinfunction "2_2") (pintype "passive"))
    )
    (net (code "40") (name "Net-(LED3-RED)") (class "Default")
      (node (ref "LED3") (pin "3") (pinfunction "RED_3") (pintype "bidirectional"))
      (node (ref "R13") (pin "2") (pinfunction "2_2") (pintype "passive"))
    )
    (net (code "41") (name "Net-(R11-S)") (class "Default")
      (node (ref "C22") (pin "1") (pinfunction "1_1") (pintype "passive"))
      (node (ref "JP22") (pin "1") (pinfunction "1_1") (pintype "passive"))
      (node (ref "R11") (pin "P$2") (pinfunction "S_P$2") (pintype "passive"))
    )
    (net (code "42") (name "Net-(R12-S)") (class "Default")
      (node (ref "C23") (pin "1") (pinfunction "1_1") (pintype "passive"))
      (node (ref "JP23") (pin "1") (pinfunction "1_1") (pintype "passive"))
      (node (ref "R12") (pin "P$2") (pinfunction "S_P$2") (pintype "passive"))
    )
    (net (code "43") (name "Net-(R22-S)") (class "Default")
      (node (ref "C35") (pin "1") (pinfunction "1_1") (pintype "passive"))
      (node (ref "JP15") (pin "1") (pinfunction "1_1") (pintype "passive"))
      (node (ref "R22") (pin "P$2") (pinfunction "S_P$2") (pintype "passive"))
    )
    (net (code "44") (name "Net-(R23-S)") (class "Default")
      (node (ref "C44") (pin "1") (pinfunction "1_1") (pintype "passive"))
      (node (ref "JP14") (pin "1") (pinfunction "1_1") (pintype "passive"))
      (node (ref "R23") (pin "P$2") (pinfunction "S_P$2") (pintype "passive"))
    )
    (net (code "45") (name "Net-(R24-S)") (class "Default")
      (node (ref "C45") (pin "1") (pinfunction "1_1") (pintype "passive"))
      (node (ref "JP20") (pin "1") (pinfunction "1_1") (pintype "passive"))
      (node (ref "R24") (pin "P$2") (pinfunction "S_P$2") (pintype "passive"))
    )
    (net (code "46") (name "Net-(R56-S)") (class "Default")
      (node (ref "C51") (pin "1") (pinfunction "1_1") (pintype "passive"))
      (node (ref "JP16") (pin "1") (pinfunction "1_1") (pintype "passive"))
      (node (ref "R56") (pin "P$2") (pinfunction "S_P$2") (pintype "passive"))
    )
    (net (code "47") (name "Net-(R57-S)") (class "Default")
      (node (ref "C52") (pin "1") (pinfunction "1_1") (pintype "passive"))
      (node (ref "JP17") (pin "1") (pinfunction "1_1") (pintype "passive"))
      (node (ref "R57") (pin "P$2") (pinfunction "S_P$2") (pintype "passive"))
    )
    (net (code "48") (name "Net-(R58-S)") (class "Default")
      (node (ref "C53") (pin "1") (pinfunction "1_1") (pintype "passive"))
      (node (ref "JP18") (pin "1") (pinfunction "1_1") (pintype "passive"))
      (node (ref "R58") (pin "P$2") (pinfunction "S_P$2") (pintype "passive"))
    )
    (net (code "49") (name "Net-(R59-S)") (class "Default")
      (node (ref "C54") (pin "1") (pinfunction "1_1") (pintype "passive"))
      (node (ref "JP19") (pin "1") (pinfunction "1_1") (pintype "passive"))
      (node (ref "R59") (pin "P$2") (pinfunction "S_P$2") (pintype "passive"))
    )
    (net (code "50") (name "Net-(R60-S)") (class "Default")
      (node (ref "C55") (pin "1") (pinfunction "1_1") (pintype "passive"))
      (node (ref "JP21") (pin "1") (pinfunction "1_1") (pintype "passive"))
      (node (ref "R60") (pin "P$2") (pinfunction "S_P$2") (pintype "passive"))
    )
    (net (code "51") (name "unconnected-(J9-2-PadP2)") (class "Default")
      (node (ref "J9") (pin "P2") (pinfunction "2_P2") (pintype "passive"))
    )
    (net (code "52") (name "unconnected-(J10-2-PadP2)") (class "Default")
      (node (ref "J10") (pin "P2") (pinfunction "2_P2") (pintype "passive"))
    )
    (net (code "53") (name "unconnected-(J11-2-PadP2)") (class "Default")
      (node (ref "J11") (pin "P2") (pinfunction "2_P2") (pintype "passive"))
    )
    (net (code "54") (name "unconnected-(J12-2-PadP2)") (class "Default")
      (node (ref "J12") (pin "P2") (pinfunction "2_P2") (pintype "passive"))
    )
  )
)
